# FPGA_HP_BANK.net
KiCad netlist of a schematic drawn in Altium Designer
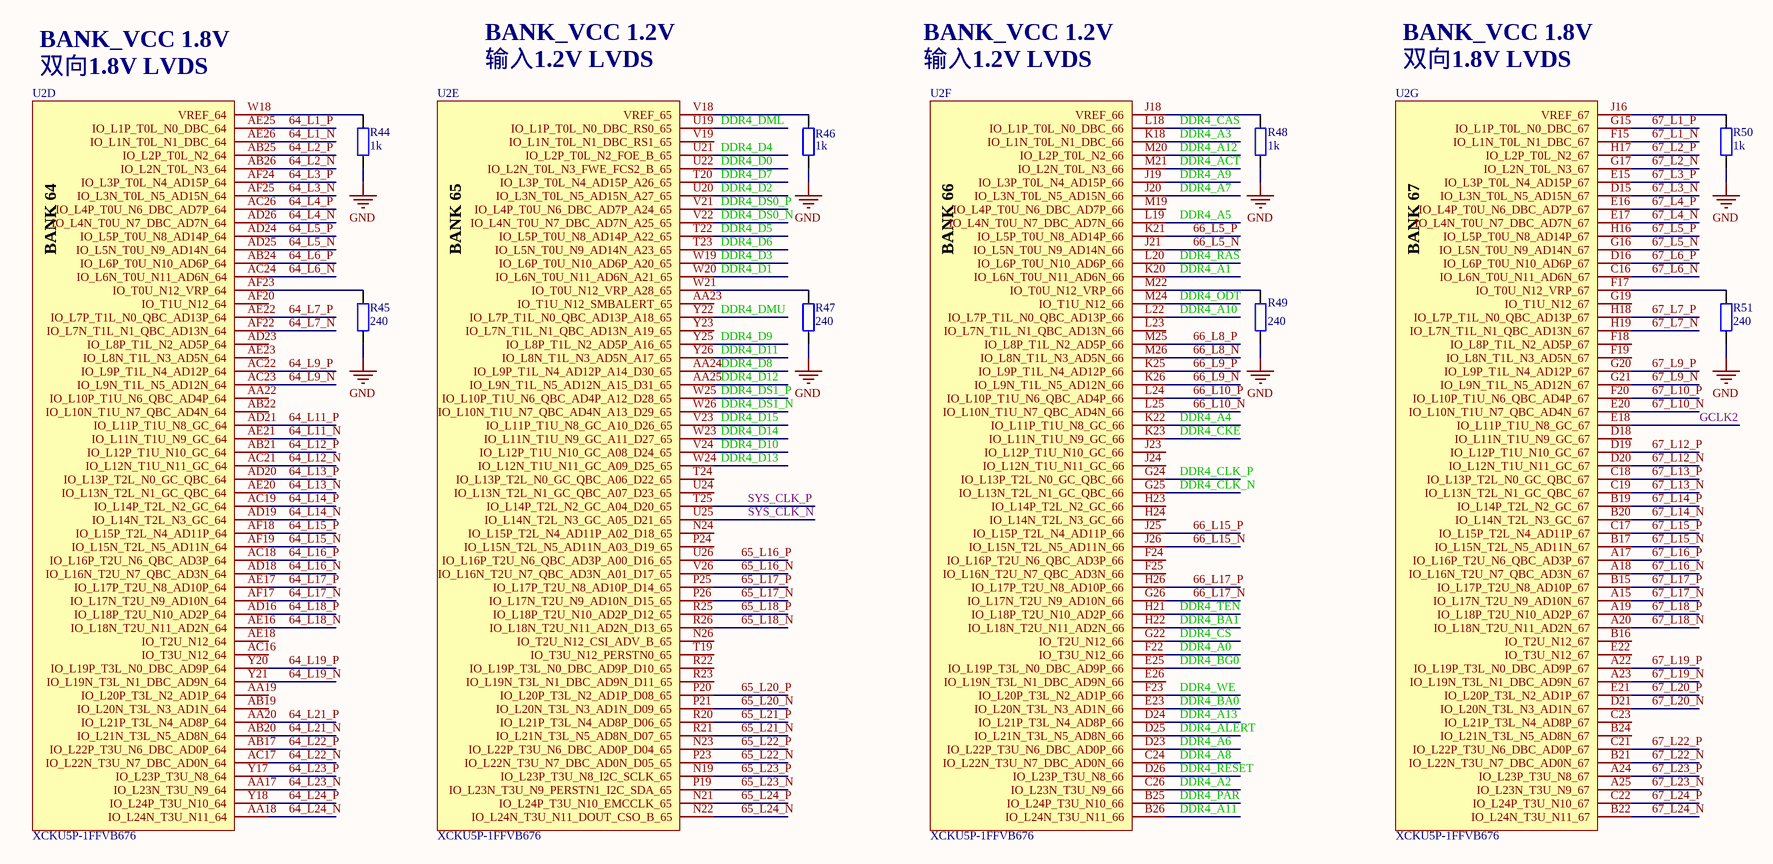
[diagram p0: FPGA HP BANK.SchDoc]

(export (version "E")
  (design (tool "Eeschema 10.0.6"))
  (components
    (comp (ref "R44") (value "1k") (footprint "0402_R_M") (libsource (lib "Common") (part "RES2")))
    (comp (ref "R45") (value "240") (footprint "0402_R_M") (libsource (lib "Common") (part "RES2")))
    (comp (ref "R46") (value "1k") (footprint "0402_R_M") (libsource (lib "Common") (part "RES2")))
    (comp (ref "R47") (value "240") (footprint "0402_R_M") (libsource (lib "Common") (part "RES2")))
    (comp (ref "R48") (value "1k") (footprint "0402_R_M") (libsource (lib "Common") (part "RES2")))
    (comp (ref "R49") (value "240") (footprint "0402_R_M") (libsource (lib "Common") (part "RES2")))
    (comp (ref "R50") (value "1k") (footprint "0402_R_M") (libsource (lib "Common") (part "RES2")))
    (comp (ref "R51") (value "240") (footprint "0402_R_M") (libsource (lib "Common") (part "RES2")))
    (comp (ref "U2") (value "XCKU5P-1FFVB676") (libsource (lib "XCKU5P-FFVB676") (part "XCKU5P-FFVB676")))
  )
  (nets
    (net (code "1") (name "/64_L1_N") (class "Default")
      (node (ref "U2") (pin "AE26") (pinfunction "IO_L1N_T0L_N1_DBC_64_AE26") (pintype "passive"))
    )
    (net (code "2") (name "/64_L1_P") (class "Default")
      (node (ref "U2") (pin "AE25") (pinfunction "IO_L1P_T0L_N0_DBC_64_AE25") (pintype "passive"))
    )
    (net (code "3") (name "/64_L2_N") (class "Default")
      (node (ref "U2") (pin "AB26") (pinfunction "IO_L2N_T0L_N3_64_AB26") (pintype "passive"))
    )
    (net (code "4") (name "/64_L2_P") (class "Default")
      (node (ref "U2") (pin "AB25") (pinfunction "IO_L2P_T0L_N2_64_AB25") (pintype "passive"))
    )
    (net (code "5") (name "/64_L3_N") (class "Default")
      (node (ref "U2") (pin "AF25") (pinfunction "IO_L3N_T0L_N5_AD15N_64_AF25") (pintype "passive"))
    )
    (net (code "6") (name "/64_L3_P") (class "Default")
      (node (ref "U2") (pin "AF24") (pinfunction "IO_L3P_T0L_N4_AD15P_64_AF24") (pintype "passive"))
    )
    (net (code "7") (name "/64_L4_N") (class "Default")
      (node (ref "U2") (pin "AD26") (pinfunction "IO_L4N_T0U_N7_DBC_AD7N_64_AD26") (pintype "passive"))
    )
    (net (code "8") (name "/64_L4_P") (class "Default")
      (node (ref "U2") (pin "AC26") (pinfunction "IO_L4P_T0U_N6_DBC_AD7P_64_AC26") (pintype "passive"))
    )
    (net (code "9") (name "/64_L5_N") (class "Default")
      (node (ref "U2") (pin "AD25") (pinfunction "IO_L5N_T0U_N9_AD14N_64_AD25") (pintype "passive"))
    )
    (net (code "10") (name "/64_L5_P") (class "Default")
      (node (ref "U2") (pin "AD24") (pinfunction "IO_L5P_T0U_N8_AD14P_64_AD24") (pintype "passive"))
    )
    (net (code "11") (name "/64_L6_N") (class "Default")
      (node (ref "U2") (pin "AC24") (pinfunction "IO_L6N_T0U_N11_AD6N_64_AC24") (pintype "passive"))
    )
    (net (code "12") (name "/64_L6_P") (class "Default")
      (node (ref "U2") (pin "AB24") (pinfunction "IO_L6P_T0U_N10_AD6P_64_AB24") (pintype "passive"))
    )
    (net (code "13") (name "/64_L7_N") (class "Default")
      (node (ref "U2") (pin "AF22") (pinfunction "IO_L7N_T1L_N1_QBC_AD13N_64_AF22") (pintype "passive"))
    )
    (net (code "14") (name "/64_L7_P") (class "Default")
      (node (ref "U2") (pin "AE22") (pinfunction "IO_L7P_T1L_N0_QBC_AD13P_64_AE22") (pintype "passive"))
    )
    (net (code "15") (name "/64_L9_N") (class "Default")
      (node (ref "U2") (pin "AC23") (pinfunction "IO_L9N_T1L_N5_AD12N_64_AC23") (pintype "passive"))
    )
    (net (code "16") (name "/64_L9_P") (class "Default")
      (node (ref "U2") (pin "AC22") (pinfunction "IO_L9P_T1L_N4_AD12P_64_AC22") (pintype "passive"))
    )
    (net (code "17") (name "/64_L11_N") (class "Default")
      (node (ref "U2") (pin "AE21") (pinfunction "IO_L11N_T1U_N9_GC_64_AE21") (pintype "passive"))
    )
    (net (code "18") (name "/64_L11_P") (class "Default")
      (node (ref "U2") (pin "AD21") (pinfunction "IO_L11P_T1U_N8_GC_64_AD21") (pintype "passive"))
    )
    (net (code "19") (name "/64_L12_N") (class "Default")
      (node (ref "U2") (pin "AC21") (pinfunction "IO_L12N_T1U_N11_GC_64_AC21") (pintype "passive"))
    )
    (net (code "20") (name "/64_L12_P") (class "Default")
      (node (ref "U2") (pin "AB21") (pinfunction "IO_L12P_T1U_N10_GC_64_AB21") (pintype "passive"))
    )
    (net (code "21") (name "/64_L13_N") (class "Default")
      (node (ref "U2") (pin "AE20") (pinfunction "IO_L13N_T2L_N1_GC_QBC_64_AE20") (pintype "passive"))
    )
    (net (code "22") (name "/64_L13_P") (class "Default")
      (node (ref "U2") (pin "AD20") (pinfunction "IO_L13P_T2L_N0_GC_QBC_64_AD20") (pintype "passive"))
    )
    (net (code "23") (name "/64_L14_N") (class "Default")
      (node (ref "U2") (pin "AD19") (pinfunction "IO_L14N_T2L_N3_GC_64_AD19") (pintype "passive"))
    )
    (net (code "24") (name "/64_L14_P") (class "Default")
      (node (ref "U2") (pin "AC19") (pinfunction "IO_L14P_T2L_N2_GC_64_AC19") (pintype "passive"))
    )
    (net (code "25") (name "/64_L15_N") (class "Default")
      (node (ref "U2") (pin "AF19") (pinfunction "IO_L15N_T2L_N5_AD11N_64_AF19") (pintype "passive"))
    )
    (net (code "26") (name "/64_L15_P") (class "Default")
      (node (ref "U2") (pin "AF18") (pinfunction "IO_L15P_T2L_N4_AD11P_64_AF18") (pintype "passive"))
    )
    (net (code "27") (name "/64_L16_N") (class "Default")
      (node (ref "U2") (pin "AD18") (pinfunction "IO_L16N_T2U_N7_QBC_AD3N_64_AD18") (pintype "passive"))
    )
    (net (code "28") (name "/64_L16_P") (class "Default")
      (node (ref "U2") (pin "AC18") (pinfunction "IO_L16P_T2U_N6_QBC_AD3P_64_AC18") (pintype "passive"))
    )
    (net (code "29") (name "/64_L17_N") (class "Default")
      (node (ref "U2") (pin "AF17") (pinfunction "IO_L17N_T2U_N9_AD10N_64_AF17") (pintype "passive"))
    )
    (net (code "30") (name "/64_L17_P") (class "Default")
      (node (ref "U2") (pin "AE17") (pinfunction "IO_L17P_T2U_N8_AD10P_64_AE17") (pintype "passive"))
    )
    (net (code "31") (name "/64_L18_N") (class "Default")
      (node (ref "U2") (pin "AE16") (pinfunction "IO_L18N_T2U_N11_AD2N_64_AE16") (pintype "passive"))
    )
    (net (code "32") (name "/64_L18_P") (class "Default")
      (node (ref "U2") (pin "AD16") (pinfunction "IO_L18P_T2U_N10_AD2P_64_AD16") (pintype "passive"))
    )
    (net (code "33") (name "/64_L19_N") (class "Default")
      (node (ref "U2") (pin "Y21") (pinfunction "IO_L19N_T3L_N1_DBC_AD9N_64_Y21") (pintype "passive"))
    )
    (net (code "34") (name "/64_L19_P") (class "Default")
      (node (ref "U2") (pin "Y20") (pinfunction "IO_L19P_T3L_N0_DBC_AD9P_64_Y20") (pintype "passive"))
    )
    (net (code "35") (name "/64_L21_N") (class "Default")
      (node (ref "U2") (pin "AB20") (pinfunction "IO_L21N_T3L_N5_AD8N_64_AB20") (pintype "passive"))
    )
    (net (code "36") (name "/64_L21_P") (class "Default")
      (node (ref "U2") (pin "AA20") (pinfunction "IO_L21P_T3L_N4_AD8P_64_AA20") (pintype "passive"))
    )
    (net (code "37") (name "/64_L22_N") (class "Default")
      (node (ref "U2") (pin "AC17") (pinfunction "IO_L22N_T3U_N7_DBC_AD0N_64_AC17") (pintype "passive"))
    )
    (net (code "38") (name "/64_L22_P") (class "Default")
      (node (ref "U2") (pin "AB17") (pinfunction "IO_L22P_T3U_N6_DBC_AD0P_64_AB17") (pintype "passive"))
    )
    (net (code "39") (name "/64_L23_N") (class "Default")
      (node (ref "U2") (pin "AA17") (pinfunction "IO_L23N_T3U_N9_64_AA17") (pintype "passive"))
    )
    (net (code "40") (name "/64_L23_P") (class "Default")
      (node (ref "U2") (pin "Y17") (pinfunction "IO_L23P_T3U_N8_64_Y17") (pintype "passive"))
    )
    (net (code "41") (name "/64_L24_N") (class "Default")
      (node (ref "U2") (pin "AA18") (pinfunction "IO_L24N_T3U_N11_64_AA18") (pintype "passive"))
    )
    (net (code "42") (name "/64_L24_P") (class "Default")
      (node (ref "U2") (pin "Y18") (pinfunction "IO_L24P_T3U_N10_64_Y18") (pintype "passive"))
    )
    (net (code "43") (name "/65_L16_N") (class "Default")
      (node (ref "U2") (pin "V26") (pinfunction "IO_L16N_T2U_N7_QBC_AD3N_A01_D17_65_V26") (pintype "passive"))
    )
    (net (code "44") (name "/65_L16_P") (class "Default")
      (node (ref "U2") (pin "U26") (pinfunction "IO_L16P_T2U_N6_QBC_AD3P_A00_D16_65_U26") (pintype "passive"))
    )
    (net (code "45") (name "/65_L17_N") (class "Default")
      (node (ref "U2") (pin "P26") (pinfunction "IO_L17N_T2U_N9_AD10N_D15_65_P26") (pintype "passive"))
    )
    (net (code "46") (name "/65_L17_P") (class "Default")
      (node (ref "U2") (pin "P25") (pinfunction "IO_L17P_T2U_N8_AD10P_D14_65_P25") (pintype "passive"))
    )
    (net (code "47") (name "/65_L18_N") (class "Default")
      (node (ref "U2") (pin "R26") (pinfunction "IO_L18N_T2U_N11_AD2N_D13_65_R26") (pintype "passive"))
    )
    (net (code "48") (name "/65_L18_P") (class "Default")
      (node (ref "U2") (pin "R25") (pinfunction "IO_L18P_T2U_N10_AD2P_D12_65_R25") (pintype "passive"))
    )
    (net (code "49") (name "/65_L20_N") (class "Default")
      (node (ref "U2") (pin "P21") (pinfunction "IO_L20N_T3L_N3_AD1N_D09_65_P21") (pintype "passive"))
    )
    (net (code "50") (name "/65_L20_P") (class "Default")
      (node (ref "U2") (pin "P20") (pinfunction "IO_L20P_T3L_N2_AD1P_D08_65_P20") (pintype "passive"))
    )
    (net (code "51") (name "/65_L21_N") (class "Default")
      (node (ref "U2") (pin "R21") (pinfunction "IO_L21N_T3L_N5_AD8N_D07_65_R21") (pintype "passive"))
    )
    (net (code "52") (name "/65_L21_P") (class "Default")
      (node (ref "U2") (pin "R20") (pinfunction "IO_L21P_T3L_N4_AD8P_D06_65_R20") (pintype "passive"))
    )
    (net (code "53") (name "/65_L22_N") (class "Default")
      (node (ref "U2") (pin "P23") (pinfunction "IO_L22N_T3U_N7_DBC_AD0N_D05_65_P23") (pintype "passive"))
    )
    (net (code "54") (name "/65_L22_P") (class "Default")
      (node (ref "U2") (pin "N23") (pinfunction "IO_L22P_T3U_N6_DBC_AD0P_D04_65_N23") (pintype "passive"))
    )
    (net (code "55") (name "/65_L23_N") (class "Default")
      (node (ref "U2") (pin "P19") (pinfunction "IO_L23N_T3U_N9_PERSTN1_I2C_SDA_65_P19") (pintype "passive"))
    )
    (net (code "56") (name "/65_L23_P") (class "Default")
      (node (ref "U2") (pin "N19") (pinfunction "IO_L23P_T3U_N8_I2C_SCLK_65_N19") (pintype "passive"))
    )
    (net (code "57") (name "/65_L24_N") (class "Default")
      (node (ref "U2") (pin "N22") (pinfunction "IO_L24N_T3U_N11_DOUT_CSO_B_65_N22") (pintype "passive"))
    )
    (net (code "58") (name "/65_L24_P") (class "Default")
      (node (ref "U2") (pin "N21") (pinfunction "IO_L24P_T3U_N10_EMCCLK_65_N21") (pintype "passive"))
    )
    (net (code "59") (name "/66_L5_N") (class "Default")
      (node (ref "U2") (pin "J21") (pinfunction "IO_L5N_T0U_N9_AD14N_66_J21") (pintype "passive"))
    )
    (net (code "60") (name "/66_L5_P") (class "Default")
      (node (ref "U2") (pin "K21") (pinfunction "IO_L5P_T0U_N8_AD14P_66_K21") (pintype "passive"))
    )
    (net (code "61") (name "/66_L8_N") (class "Default")
      (node (ref "U2") (pin "M26") (pinfunction "IO_L8N_T1L_N3_AD5N_66_M26") (pintype "passive"))
    )
    (net (code "62") (name "/66_L8_P") (class "Default")
      (node (ref "U2") (pin "M25") (pinfunction "IO_L8P_T1L_N2_AD5P_66_M25") (pintype "passive"))
    )
    (net (code "63") (name "/66_L9_N") (class "Default")
      (node (ref "U2") (pin "K26") (pinfunction "IO_L9N_T1L_N5_AD12N_66_K26") (pintype "passive"))
    )
    (net (code "64") (name "/66_L9_P") (class "Default")
      (node (ref "U2") (pin "K25") (pinfunction "IO_L9P_T1L_N4_AD12P_66_K25") (pintype "passive"))
    )
    (net (code "65") (name "/66_L10_N") (class "Default")
      (node (ref "U2") (pin "L25") (pinfunction "IO_L10N_T1U_N7_QBC_AD4N_66_L25") (pintype "passive"))
    )
    (net (code "66") (name "/66_L10_P") (class "Default")
      (node (ref "U2") (pin "L24") (pinfunction "IO_L10P_T1U_N6_QBC_AD4P_66_L24") (pintype "passive"))
    )
    (net (code "67") (name "/66_L15_N") (class "Default")
      (node (ref "U2") (pin "J26") (pinfunction "IO_L15N_T2L_N5_AD11N_66_J26") (pintype "passive"))
    )
    (net (code "68") (name "/66_L15_P") (class "Default")
      (node (ref "U2") (pin "J25") (pinfunction "IO_L15P_T2L_N4_AD11P_66_J25") (pintype "passive"))
    )
    (net (code "69") (name "/66_L17_N") (class "Default")
      (node (ref "U2") (pin "G26") (pinfunction "IO_L17N_T2U_N9_AD10N_66_G26") (pintype "passive"))
    )
    (net (code "70") (name "/66_L17_P") (class "Default")
      (node (ref "U2") (pin "H26") (pinfunction "IO_L17P_T2U_N8_AD10P_66_H26") (pintype "passive"))
    )
    (net (code "71") (name "/67_L1_N") (class "Default")
      (node (ref "U2") (pin "F15") (pinfunction "IO_L1N_T0L_N1_DBC_67_F15") (pintype "passive"))
    )
    (net (code "72") (name "/67_L1_P") (class "Default")
      (node (ref "U2") (pin "G15") (pinfunction "IO_L1P_T0L_N0_DBC_67_G15") (pintype "passive"))
    )
    (net (code "73") (name "/67_L2_N") (class "Default")
      (node (ref "U2") (pin "G17") (pinfunction "IO_L2N_T0L_N3_67_G17") (pintype "passive"))
    )
    (net (code "74") (name "/67_L2_P") (class "Default")
      (node (ref "U2") (pin "H17") (pinfunction "IO_L2P_T0L_N2_67_H17") (pintype "passive"))
    )
    (net (code "75") (name "/67_L3_N") (class "Default")
      (node (ref "U2") (pin "D15") (pinfunction "IO_L3N_T0L_N5_AD15N_67_D15") (pintype "passive"))
    )
    (net (code "76") (name "/67_L3_P") (class "Default")
      (node (ref "U2") (pin "E15") (pinfunction "IO_L3P_T0L_N4_AD15P_67_E15") (pintype "passive"))
    )
    (net (code "77") (name "/67_L4_N") (class "Default")
      (node (ref "U2") (pin "E17") (pinfunction "IO_L4N_T0U_N7_DBC_AD7N_67_E17") (pintype "passive"))
    )
    (net (code "78") (name "/67_L4_P") (class "Default")
      (node (ref "U2") (pin "E16") (pinfunction "IO_L4P_T0U_N6_DBC_AD7P_67_E16") (pintype "passive"))
    )
    (net (code "79") (name "/67_L5_N") (class "Default")
      (node (ref "U2") (pin "G16") (pinfunction "IO_L5N_T0U_N9_AD14N_67_G16") (pintype "passive"))
    )
    (net (code "80") (name "/67_L5_P") (class "Default")
      (node (ref "U2") (pin "H16") (pinfunction "IO_L5P_T0U_N8_AD14P_67_H16") (pintype "passive"))
    )
    (net (code "81") (name "/67_L6_N") (class "Default")
      (node (ref "U2") (pin "C16") (pinfunction "IO_L6N_T0U_N11_AD6N_67_C16") (pintype "passive"))
    )
    (net (code "82") (name "/67_L6_P") (class "Default")
      (node (ref "U2") (pin "D16") (pinfunction "IO_L6P_T0U_N10_AD6P_67_D16") (pintype "passive"))
    )
    (net (code "83") (name "/67_L7_N") (class "Default")
      (node (ref "U2") (pin "H19") (pinfunction "IO_L7N_T1L_N1_QBC_AD13N_67_H19") (pintype "passive"))
    )
    (net (code "84") (name "/67_L7_P") (class "Default")
      (node (ref "U2") (pin "H18") (pinfunction "IO_L7P_T1L_N0_QBC_AD13P_67_H18") (pintype "passive"))
    )
    (net (code "85") (name "/67_L9_N") (class "Default")
      (node (ref "U2") (pin "G21") (pinfunction "IO_L9N_T1L_N5_AD12N_67_G21") (pintype "passive"))
    )
    (net (code "86") (name "/67_L9_P") (class "Default")
      (node (ref "U2") (pin "G20") (pinfunction "IO_L9P_T1L_N4_AD12P_67_G20") (pintype "passive"))
    )
    (net (code "87") (name "/67_L10_N") (class "Default")
      (node (ref "U2") (pin "E20") (pinfunction "IO_L10N_T1U_N7_QBC_AD4N_67_E20") (pintype "passive"))
    )
    (net (code "88") (name "/67_L10_P") (class "Default")
      (node (ref "U2") (pin "F20") (pinfunction "IO_L10P_T1U_N6_QBC_AD4P_67_F20") (pintype "passive"))
    )
    (net (code "89") (name "/67_L12_N") (class "Default")
      (node (ref "U2") (pin "D20") (pinfunction "IO_L12N_T1U_N11_GC_67_D20") (pintype "passive"))
    )
    (net (code "90") (name "/67_L12_P") (class "Default")
      (node (ref "U2") (pin "D19") (pinfunction "IO_L12P_T1U_N10_GC_67_D19") (pintype "passive"))
    )
    (net (code "91") (name "/67_L13_N") (class "Default")
      (node (ref "U2") (pin "C19") (pinfunction "IO_L13N_T2L_N1_GC_QBC_67_C19") (pintype "passive"))
    )
    (net (code "92") (name "/67_L13_P") (class "Default")
      (node (ref "U2") (pin "C18") (pinfunction "IO_L13P_T2L_N0_GC_QBC_67_C18") (pintype "passive"))
    )
    (net (code "93") (name "/67_L14_N") (class "Default")
      (node (ref "U2") (pin "B20") (pinfunction "IO_L14N_T2L_N3_GC_67_B20") (pintype "passive"))
    )
    (net (code "94") (name "/67_L14_P") (class "Default")
      (node (ref "U2") (pin "B19") (pinfunction "IO_L14P_T2L_N2_GC_67_B19") (pintype "passive"))
    )
    (net (code "95") (name "/67_L15_N") (class "Default")
      (node (ref "U2") (pin "B17") (pinfunction "IO_L15N_T2L_N5_AD11N_67_B17") (pintype "passive"))
    )
    (net (code "96") (name "/67_L15_P") (class "Default")
      (node (ref "U2") (pin "C17") (pinfunction "IO_L15P_T2L_N4_AD11P_67_C17") (pintype "passive"))
    )
    (net (code "97") (name "/67_L16_N") (class "Default")
      (node (ref "U2") (pin "A18") (pinfunction "IO_L16N_T2U_N7_QBC_AD3N_67_A18") (pintype "passive"))
    )
    (net (code "98") (name "/67_L16_P") (class "Default")
      (node (ref "U2") (pin "A17") (pinfunction "IO_L16P_T2U_N6_QBC_AD3P_67_A17") (pintype "passive"))
    )
    (net (code "99") (name "/67_L17_N") (class "Default")
      (node (ref "U2") (pin "A15") (pinfunction "IO_L17N_T2U_N9_AD10N_67_A15") (pintype "passive"))
    )
    (net (code "100") (name "/67_L17_P") (class "Default")
      (node (ref "U2") (pin "B15") (pinfunction "IO_L17P_T2U_N8_AD10P_67_B15") (pintype "passive"))
    )
    (net (code "101") (name "/67_L18_N") (class "Default")
      (node (ref "U2") (pin "A20") (pinfunction "IO_L18N_T2U_N11_AD2N_67_A20") (pintype "passive"))
    )
    (net (code "102") (name "/67_L18_P") (class "Default")
      (node (ref "U2") (pin "A19") (pinfunction "IO_L18P_T2U_N10_AD2P_67_A19") (pintype "passive"))
    )
    (net (code "103") (name "/67_L19_N") (class "Default")
      (node (ref "U2") (pin "A23") (pinfunction "IO_L19N_T3L_N1_DBC_AD9N_67_A23") (pintype "passive"))
    )
    (net (code "104") (name "/67_L19_P") (class "Default")
      (node (ref "U2") (pin "A22") (pinfunction "IO_L19P_T3L_N0_DBC_AD9P_67_A22") (pintype "passive"))
    )
    (net (code "105") (name "/67_L20_N") (class "Default")
      (node (ref "U2") (pin "D21") (pinfunction "IO_L20N_T3L_N3_AD1N_67_D21") (pintype "passive"))
    )
    (net (code "106") (name "/67_L20_P") (class "Default")
      (node (ref "U2") (pin "E21") (pinfunction "IO_L20P_T3L_N2_AD1P_67_E21") (pintype "passive"))
    )
    (net (code "107") (name "/67_L22_N") (class "Default")
      (node (ref "U2") (pin "B21") (pinfunction "IO_L22N_T3U_N7_DBC_AD0N_67_B21") (pintype "passive"))
    )
    (net (code "108") (name "/67_L22_P") (class "Default")
      (node (ref "U2") (pin "C21") (pinfunction "IO_L22P_T3U_N6_DBC_AD0P_67_C21") (pintype "passive"))
    )
    (net (code "109") (name "/67_L23_N") (class "Default")
      (node (ref "U2") (pin "A25") (pinfunction "IO_L23N_T3U_N9_67_A25") (pintype "passive"))
    )
    (net (code "110") (name "/67_L23_P") (class "Default")
      (node (ref "U2") (pin "A24") (pinfunction "IO_L23P_T3U_N8_67_A24") (pintype "passive"))
    )
    (net (code "111") (name "/67_L24_N") (class "Default")
      (node (ref "U2") (pin "B22") (pinfunction "IO_L24N_T3U_N11_67_B22") (pintype "passive"))
    )
    (net (code "112") (name "/67_L24_P") (class "Default")
      (node (ref "U2") (pin "C22") (pinfunction "IO_L24P_T3U_N10_67_C22") (pintype "passive"))
    )
    (net (code "113") (name "/DDR4_A0") (class "Default")
      (node (ref "U2") (pin "F22") (pinfunction "IO_T3U_N12_66_F22") (pintype "passive"))
    )
    (net (code "114") (name "/DDR4_A1") (class "Default")
      (node (ref "U2") (pin "K20") (pinfunction "IO_L6N_T0U_N11_AD6N_66_K20") (pintype "passive"))
    )
    (net (code "115") (name "/DDR4_A2") (class "Default")
      (node (ref "U2") (pin "C26") (pinfunction "IO_L23N_T3U_N9_66_C26") (pintype "passive"))
    )
    (net (code "116") (name "/DDR4_A3") (class "Default")
      (node (ref "U2") (pin "K18") (pinfunction "IO_L1N_T0L_N1_DBC_66_K18") (pintype "passive"))
    )
    (net (code "117") (name "/DDR4_A4") (class "Default")
      (node (ref "U2") (pin "K22") (pinfunction "IO_L11P_T1U_N8_GC_66_K22") (pintype "passive"))
    )
    (net (code "118") (name "/DDR4_A5") (class "Default")
      (node (ref "U2") (pin "L19") (pinfunction "IO_L4N_T0U_N7_DBC_AD7N_66_L19") (pintype "passive"))
    )
    (net (code "119") (name "/DDR4_A6") (class "Default")
      (node (ref "U2") (pin "D23") (pinfunction "IO_L22P_T3U_N6_DBC_AD0P_66_D23") (pintype "passive"))
    )
    (net (code "120") (name "/DDR4_A7") (class "Default")
      (node (ref "U2") (pin "J20") (pinfunction "IO_L3N_T0L_N5_AD15N_66_J20") (pintype "passive"))
    )
    (net (code "121") (name "/DDR4_A8") (class "Default")
      (node (ref "U2") (pin "C24") (pinfunction "IO_L22N_T3U_N7_DBC_AD0N_66_C24") (pintype "passive"))
    )
    (net (code "122") (name "/DDR4_A9") (class "Default")
      (node (ref "U2") (pin "J19") (pinfunction "IO_L3P_T0L_N4_AD15P_66_J19") (pintype "passive"))
    )
    (net (code "123") (name "/DDR4_A10") (class "Default")
      (node (ref "U2") (pin "L22") (pinfunction "IO_L7P_T1L_N0_QBC_AD13P_66_L22") (pintype "passive"))
    )
    (net (code "124") (name "/DDR4_A11") (class "Default")
      (node (ref "U2") (pin "B26") (pinfunction "IO_L24N_T3U_N11_66_B26") (pintype "passive"))
    )
    (net (code "125") (name "/DDR4_A12") (class "Default")
      (node (ref "U2") (pin "M20") (pinfunction "IO_L2P_T0L_N2_66_M20") (pintype "passive"))
    )
    (net (code "126") (name "/DDR4_A13") (class "Default")
      (node (ref "U2") (pin "D24") (pinfunction "IO_L21P_T3L_N4_AD8P_66_D24") (pintype "passive"))
    )
    (net (code "127") (name "/DDR4_ACT") (class "Default")
      (node (ref "U2") (pin "M21") (pinfunction "IO_L2N_T0L_N3_66_M21") (pintype "passive"))
    )
    (net (code "128") (name "/DDR4_ALERT") (class "Default")
      (node (ref "U2") (pin "D25") (pinfunction "IO_L21N_T3L_N5_AD8N_66_D25") (pintype "passive"))
    )
    (net (code "129") (name "/DDR4_BA0") (class "Default")
      (node (ref "U2") (pin "E23") (pinfunction "IO_L20N_T3L_N3_AD1N_66_E23") (pintype "passive"))
    )
    (net (code "130") (name "/DDR4_BA1") (class "Default")
      (node (ref "U2") (pin "H22") (pinfunction "IO_L18N_T2U_N11_AD2N_66_H22") (pintype "passive"))
    )
    (net (code "131") (name "/DDR4_BG0") (class "Default")
      (node (ref "U2") (pin "E25") (pinfunction "IO_L19P_T3L_N0_DBC_AD9P_66_E25") (pintype "passive"))
    )
    (net (code "132") (name "/DDR4_CAS") (class "Default")
      (node (ref "U2") (pin "L18") (pinfunction "IO_L1P_T0L_N0_DBC_66_L18") (pintype "passive"))
    )
    (net (code "133") (name "/DDR4_CKE") (class "Default")
      (node (ref "U2") (pin "K23") (pinfunction "IO_L11N_T1U_N9_GC_66_K23") (pintype "passive"))
    )
    (net (code "134") (name "/DDR4_CLK_N") (class "Default")
      (node (ref "U2") (pin "G25") (pinfunction "IO_L13N_T2L_N1_GC_QBC_66_G25") (pintype "passive"))
    )
    (net (code "135") (name "/DDR4_CLK_P") (class "Default")
      (node (ref "U2") (pin "G24") (pinfunction "IO_L13P_T2L_N0_GC_QBC_66_G24") (pintype "passive"))
    )
    (net (code "136") (name "/DDR4_CS") (class "Default")
      (node (ref "U2") (pin "G22") (pinfunction "IO_T2U_N12_66_G22") (pintype "passive"))
    )
    (net (code "137") (name "/DDR4_D0") (class "Default")
      (node (ref "U2") (pin "U22") (pinfunction "IO_L2N_T0L_N3_FWE_FCS2_B_65_U22") (pintype "passive"))
    )
    (net (code "138") (name "/DDR4_D1") (class "Default")
      (node (ref "U2") (pin "W20") (pinfunction "IO_L6N_T0U_N11_AD6N_A21_65_W20") (pintype "passive"))
    )
    (net (code "139") (name "/DDR4_D2") (class "Default")
      (node (ref "U2") (pin "U20") (pinfunction "IO_L3N_T0L_N5_AD15N_A27_65_U20") (pintype "passive"))
    )
    (net (code "140") (name "/DDR4_D3") (class "Default")
      (node (ref "U2") (pin "W19") (pinfunction "IO_L6P_T0U_N10_AD6P_A20_65_W19") (pintype "passive"))
    )
    (net (code "141") (name "/DDR4_D4") (class "Default")
      (node (ref "U2") (pin "U21") (pinfunction "IO_L2P_T0L_N2_FOE_B_65_U21") (pintype "passive"))
    )
    (net (code "142") (name "/DDR4_D5") (class "Default")
      (node (ref "U2") (pin "T22") (pinfunction "IO_L5P_T0U_N8_AD14P_A22_65_T22") (pintype "passive"))
    )
    (net (code "143") (name "/DDR4_D6") (class "Default")
      (node (ref "U2") (pin "T23") (pinfunction "IO_L5N_T0U_N9_AD14N_A23_65_T23") (pintype "passive"))
    )
    (net (code "144") (name "/DDR4_D7") (class "Default")
      (node (ref "U2") (pin "T20") (pinfunction "IO_L3P_T0L_N4_AD15P_A26_65_T20") (pintype "passive"))
    )
    (net (code "145") (name "/DDR4_D8") (class "Default")
      (node (ref "U2") (pin "AA24") (pinfunction "IO_L9P_T1L_N4_AD12P_A14_D30_65_AA24") (pintype "passive"))
    )
    (net (code "146") (name "/DDR4_D9") (class "Default")
      (node (ref "U2") (pin "Y25") (pinfunction "IO_L8P_T1L_N2_AD5P_A16_65_Y25") (pintype "passive"))
    )
    (net (code "147") (name "/DDR4_D10") (class "Default")
      (node (ref "U2") (pin "V24") (pinfunction "IO_L12P_T1U_N10_GC_A08_D24_65_V24") (pintype "passive"))
    )
    (net (code "148") (name "/DDR4_D11") (class "Default")
      (node (ref "U2") (pin "Y26") (pinfunction "IO_L8N_T1L_N3_AD5N_A17_65_Y26") (pintype "passive"))
    )
    (net (code "149") (name "/DDR4_D12") (class "Default")
      (node (ref "U2") (pin "AA25") (pinfunction "IO_L9N_T1L_N5_AD12N_A15_D31_65_AA25") (pintype "passive"))
    )
    (net (code "150") (name "/DDR4_D13") (class "Default")
      (node (ref "U2") (pin "W24") (pinfunction "IO_L12N_T1U_N11_GC_A09_D25_65_W24") (pintype "passive"))
    )
    (net (code "151") (name "/DDR4_D14") (class "Default")
      (node (ref "U2") (pin "W23") (pinfunction "IO_L11N_T1U_N9_GC_A11_D27_65_W23") (pintype "passive"))
    )
    (net (code "152") (name "/DDR4_D15") (class "Default")
      (node (ref "U2") (pin "V23") (pinfunction "IO_L11P_T1U_N8_GC_A10_D26_65_V23") (pintype "passive"))
    )
    (net (code "153") (name "/DDR4_DML") (class "Default")
      (node (ref "U2") (pin "U19") (pinfunction "IO_L1P_T0L_N0_DBC_RS0_65_U19") (pintype "passive"))
    )
    (net (code "154") (name "/DDR4_DMU") (class "Default")
      (node (ref "U2") (pin "Y22") (pinfunction "IO_L7P_T1L_N0_QBC_AD13P_A18_65_Y22") (pintype "passive"))
    )
    (net (code "155") (name "/DDR4_DS0_N") (class "Default")
      (node (ref "U2") (pin "V22") (pinfunction "IO_L4N_T0U_N7_DBC_AD7N_A25_65_V22") (pintype "passive"))
    )
    (net (code "156") (name "/DDR4_DS0_P") (class "Default")
      (node (ref "U2") (pin "V21") (pinfunction "IO_L4P_T0U_N6_DBC_AD7P_A24_65_V21") (pintype "passive"))
    )
    (net (code "157") (name "/DDR4_DS1_N") (class "Default")
      (node (ref "U2") (pin "W26") (pinfunction "IO_L10N_T1U_N7_QBC_AD4N_A13_D29_65_W26") (pintype "passive"))
    )
    (net (code "158") (name "/DDR4_DS1_P") (class "Default")
      (node (ref "U2") (pin "W25") (pinfunction "IO_L10P_T1U_N6_QBC_AD4P_A12_D28_65_W25") (pintype "passive"))
    )
    (net (code "159") (name "/DDR4_ODT") (class "Default")
      (node (ref "U2") (pin "M24") (pinfunction "IO_T1U_N12_66_M24") (pintype "passive"))
    )
    (net (code "160") (name "/DDR4_PAR") (class "Default")
      (node (ref "U2") (pin "B25") (pinfunction "IO_L24P_T3U_N10_66_B25") (pintype "passive"))
    )
    (net (code "161") (name "/DDR4_RAS") (class "Default")
      (node (ref "U2") (pin "L20") (pinfunction "IO_L6P_T0U_N10_AD6P_66_L20") (pintype "passive"))
    )
    (net (code "162") (name "/DDR4_RESET") (class "Default")
      (node (ref "U2") (pin "D26") (pinfunction "IO_L23P_T3U_N8_66_D26") (pintype "passive"))
    )
    (net (code "163") (name "/DDR4_TEN") (class "Default")
      (node (ref "U2") (pin "H21") (pinfunction "IO_L18P_T2U_N10_AD2P_66_H21") (pintype "passive"))
    )
    (net (code "164") (name "/DDR4_WE") (class "Default")
      (node (ref "U2") (pin "F23") (pinfunction "IO_L20P_T3L_N2_AD1P_66_F23") (pintype "passive"))
    )
    (net (code "165") (name "/GCLK2") (class "Default")
      (node (ref "U2") (pin "E18") (pinfunction "IO_L11P_T1U_N8_GC_67_E18") (pintype "passive"))
    )
    (net (code "166") (name "/SYS_CLK_N") (class "Default")
      (node (ref "U2") (pin "U25") (pinfunction "IO_L14N_T2L_N3_GC_A05_D21_65_U25") (pintype "passive"))
    )
    (net (code "167") (name "/SYS_CLK_P") (class "Default")
      (node (ref "U2") (pin "T25") (pinfunction "IO_L14P_T2L_N2_GC_A04_D20_65_T25") (pintype "passive"))
    )
    (net (code "168") (name "GND") (class "Default")
      (node (ref "R44") (pin "2") (pintype "passive"))
      (node (ref "R45") (pin "2") (pintype "passive"))
      (node (ref "R46") (pin "2") (pintype "passive"))
      (node (ref "R47") (pin "2") (pintype "passive"))
      (node (ref "R48") (pin "2") (pintype "passive"))
      (node (ref "R49") (pin "2") (pintype "passive"))
      (node (ref "R50") (pin "2") (pintype "passive"))
      (node (ref "R51") (pin "2") (pintype "passive"))
    )
    (net (code "169") (name "Net-(U2D-IO_T0U_N12_VRP_64)") (class "Default")
      (node (ref "R45") (pin "1") (pintype "passive"))
      (node (ref "U2") (pin "AF23") (pinfunction "IO_T0U_N12_VRP_64_AF23") (pintype "passive"))
    )
    (net (code "170") (name "Net-(U2D-VREF_64)") (class "Default")
      (node (ref "R44") (pin "1") (pintype "passive"))
      (node (ref "U2") (pin "W18") (pinfunction "VREF_64_W18") (pintype "passive"))
    )
    (net (code "171") (name "Net-(U2E-IO_T0U_N12_VRP_A28_65)") (class "Default")
      (node (ref "R47") (pin "1") (pintype "passive"))
      (node (ref "U2") (pin "W21") (pinfunction "IO_T0U_N12_VRP_A28_65_W21") (pintype "passive"))
    )
    (net (code "172") (name "Net-(U2E-VREF_65)") (class "Default")
      (node (ref "R46") (pin "1") (pintype "passive"))
      (node (ref "U2") (pin "V18") (pinfunction "VREF_65_V18") (pintype "passive"))
    )
    (net (code "173") (name "Net-(U2F-IO_T0U_N12_VRP_66)") (class "Default")
      (node (ref "R49") (pin "1") (pintype "passive"))
      (node (ref "U2") (pin "M22") (pinfunction "IO_T0U_N12_VRP_66_M22") (pintype "passive"))
    )
    (net (code "174") (name "Net-(U2F-VREF_66)") (class "Default")
      (node (ref "R48") (pin "1") (pintype "passive"))
      (node (ref "U2") (pin "J18") (pinfunction "VREF_66_J18") (pintype "passive"))
    )
    (net (code "175") (name "Net-(U2G-IO_T0U_N12_VRP_67)") (class "Default")
      (node (ref "R51") (pin "1") (pintype "passive"))
      (node (ref "U2") (pin "F17") (pinfunction "IO_T0U_N12_VRP_67_F17") (pintype "passive"))
    )
    (net (code "176") (name "Net-(U2G-VREF_67)") (class "Default")
      (node (ref "R50") (pin "1") (pintype "passive"))
      (node (ref "U2") (pin "J16") (pinfunction "VREF_67_J16") (pintype "passive"))
    )
    (net (code "177") (name "unconnected-(U2D-IO_L8N_T1L_N3_AD5N_64-PadAE23)") (class "Default")
      (node (ref "U2") (pin "AE23") (pinfunction "IO_L8N_T1L_N3_AD5N_64_AE23") (pintype "passive"))
    )
    (net (code "178") (name "unconnected-(U2D-IO_L8P_T1L_N2_AD5P_64-PadAD23)") (class "Default")
      (node (ref "U2") (pin "AD23") (pinfunction "IO_L8P_T1L_N2_AD5P_64_AD23") (pintype "passive"))
    )
    (net (code "179") (name "unconnected-(U2D-IO_L10N_T1U_N7_QBC_AD4N_64-PadAB22)") (class "Default")
      (node (ref "U2") (pin "AB22") (pinfunction "IO_L10N_T1U_N7_QBC_AD4N_64_AB22") (pintype "passive"))
    )
    (net (code "180") (name "unconnected-(U2D-IO_L10P_T1U_N6_QBC_AD4P_64-PadAA22)") (class "Default")
      (node (ref "U2") (pin "AA22") (pinfunction "IO_L10P_T1U_N6_QBC_AD4P_64_AA22") (pintype "passive"))
    )
    (net (code "181") (name "unconnected-(U2D-IO_L20N_T3L_N3_AD1N_64-PadAB19)") (class "Default")
      (node (ref "U2") (pin "AB19") (pinfunction "IO_L20N_T3L_N3_AD1N_64_AB19") (pintype "passive"))
    )
    (net (code "182") (name "unconnected-(U2D-IO_L20P_T3L_N2_AD1P_64-PadAA19)") (class "Default")
      (node (ref "U2") (pin "AA19") (pinfunction "IO_L20P_T3L_N2_AD1P_64_AA19") (pintype "passive"))
    )
    (net (code "183") (name "unconnected-(U2D-IO_T1U_N12_64-PadAF20)") (class "Default")
      (node (ref "U2") (pin "AF20") (pinfunction "IO_T1U_N12_64_AF20") (pintype "passive"))
    )
    (net (code "184") (name "unconnected-(U2D-IO_T2U_N12_64-PadAE18)") (class "Default")
      (node (ref "U2") (pin "AE18") (pinfunction "IO_T2U_N12_64_AE18") (pintype "passive"))
    )
    (net (code "185") (name "unconnected-(U2D-IO_T3U_N12_64-PadAC16)") (class "Default")
      (node (ref "U2") (pin "AC16") (pinfunction "IO_T3U_N12_64_AC16") (pintype "passive"))
    )
    (net (code "186") (name "unconnected-(U2E-IO_L1N_T0L_N1_DBC_RS1_65-PadV19)") (class "Default")
      (node (ref "U2") (pin "V19") (pinfunction "IO_L1N_T0L_N1_DBC_RS1_65_V19") (pintype "passive"))
    )
    (net (code "187") (name "unconnected-(U2E-IO_L7N_T1L_N1_QBC_AD13N_A19_65-PadY23)") (class "Default")
      (node (ref "U2") (pin "Y23") (pinfunction "IO_L7N_T1L_N1_QBC_AD13N_A19_65_Y23") (pintype "passive"))
    )
    (net (code "188") (name "unconnected-(U2E-IO_L13N_T2L_N1_GC_QBC_A07_D23_65-PadU24)") (class "Default")
      (node (ref "U2") (pin "U24") (pinfunction "IO_L13N_T2L_N1_GC_QBC_A07_D23_65_U24") (pintype "passive"))
    )
    (net (code "189") (name "unconnected-(U2E-IO_L13P_T2L_N0_GC_QBC_A06_D22_65-PadT24)") (class "Default")
      (node (ref "U2") (pin "T24") (pinfunction "IO_L13P_T2L_N0_GC_QBC_A06_D22_65_T24") (pintype "passive"))
    )
    (net (code "190") (name "unconnected-(U2E-IO_L15N_T2L_N5_AD11N_A03_D19_65-PadP24)") (class "Default")
      (node (ref "U2") (pin "P24") (pinfunction "IO_L15N_T2L_N5_AD11N_A03_D19_65_P24") (pintype "passive"))
    )
    (net (code "191") (name "unconnected-(U2E-IO_L15P_T2L_N4_AD11P_A02_D18_65-PadN24)") (class "Default")
      (node (ref "U2") (pin "N24") (pinfunction "IO_L15P_T2L_N4_AD11P_A02_D18_65_N24") (pintype "passive"))
    )
    (net (code "192") (name "unconnected-(U2E-IO_L19N_T3L_N1_DBC_AD9N_D11_65-PadR23)") (class "Default")
      (node (ref "U2") (pin "R23") (pinfunction "IO_L19N_T3L_N1_DBC_AD9N_D11_65_R23") (pintype "passive"))
    )
    (net (code "193") (name "unconnected-(U2E-IO_L19P_T3L_N0_DBC_AD9P_D10_65-PadR22)") (class "Default")
      (node (ref "U2") (pin "R22") (pinfunction "IO_L19P_T3L_N0_DBC_AD9P_D10_65_R22") (pintype "passive"))
    )
    (net (code "194") (name "unconnected-(U2E-IO_T1U_N12_SMBALERT_65-PadAA23)") (class "Default")
      (node (ref "U2") (pin "AA23") (pinfunction "IO_T1U_N12_SMBALERT_65_AA23") (pintype "passive"))
    )
    (net (code "195") (name "unconnected-(U2E-IO_T2U_N12_CSI_ADV_B_65-PadN26)") (class "Default")
      (node (ref "U2") (pin "N26") (pinfunction "IO_T2U_N12_CSI_ADV_B_65_N26") (pintype "passive"))
    )
    (net (code "196") (name "unconnected-(U2E-IO_T3U_N12_PERSTN0_65-PadT19)") (class "Default")
      (node (ref "U2") (pin "T19") (pinfunction "IO_T3U_N12_PERSTN0_65_T19") (pintype "passive"))
    )
    (net (code "197") (name "unconnected-(U2F-IO_L4P_T0U_N6_DBC_AD7P_66-PadM19)") (class "Default")
      (node (ref "U2") (pin "M19") (pinfunction "IO_L4P_T0U_N6_DBC_AD7P_66_M19") (pintype "passive"))
    )
    (net (code "198") (name "unconnected-(U2F-IO_L7N_T1L_N1_QBC_AD13N_66-PadL23)") (class "Default")
      (node (ref "U2") (pin "L23") (pinfunction "IO_L7N_T1L_N1_QBC_AD13N_66_L23") (pintype "passive"))
    )
    (net (code "199") (name "unconnected-(U2F-IO_L12N_T1U_N11_GC_66-PadJ24)") (class "Default")
      (node (ref "U2") (pin "J24") (pinfunction "IO_L12N_T1U_N11_GC_66_J24") (pintype "passive"))
    )
    (net (code "200") (name "unconnected-(U2F-IO_L12P_T1U_N10_GC_66-PadJ23)") (class "Default")
      (node (ref "U2") (pin "J23") (pinfunction "IO_L12P_T1U_N10_GC_66_J23") (pintype "passive"))
    )
    (net (code "201") (name "unconnected-(U2F-IO_L14N_T2L_N3_GC_66-PadH24)") (class "Default")
      (node (ref "U2") (pin "H24") (pinfunction "IO_L14N_T2L_N3_GC_66_H24") (pintype "passive"))
    )
    (net (code "202") (name "unconnected-(U2F-IO_L14P_T2L_N2_GC_66-PadH23)") (class "Default")
      (node (ref "U2") (pin "H23") (pinfunction "IO_L14P_T2L_N2_GC_66_H23") (pintype "passive"))
    )
    (net (code "203") (name "unconnected-(U2F-IO_L16N_T2U_N7_QBC_AD3N_66-PadF25)") (class "Default")
      (node (ref "U2") (pin "F25") (pinfunction "IO_L16N_T2U_N7_QBC_AD3N_66_F25") (pintype "passive"))
    )
    (net (code "204") (name "unconnected-(U2F-IO_L16P_T2U_N6_QBC_AD3P_66-PadF24)") (class "Default")
      (node (ref "U2") (pin "F24") (pinfunction "IO_L16P_T2U_N6_QBC_AD3P_66_F24") (pintype "passive"))
    )
    (net (code "205") (name "unconnected-(U2F-IO_L19N_T3L_N1_DBC_AD9N_66-PadE26)") (class "Default")
      (node (ref "U2") (pin "E26") (pinfunction "IO_L19N_T3L_N1_DBC_AD9N_66_E26") (pintype "passive"))
    )
    (net (code "206") (name "unconnected-(U2G-IO_L8N_T1L_N3_AD5N_67-PadF19)") (class "Default")
      (node (ref "U2") (pin "F19") (pinfunction "IO_L8N_T1L_N3_AD5N_67_F19") (pintype "passive"))
    )
    (net (code "207") (name "unconnected-(U2G-IO_L8P_T1L_N2_AD5P_67-PadF18)") (class "Default")
      (node (ref "U2") (pin "F18") (pinfunction "IO_L8P_T1L_N2_AD5P_67_F18") (pintype "passive"))
    )
    (net (code "208") (name "unconnected-(U2G-IO_L11N_T1U_N9_GC_67-PadD18)") (class "Default")
      (node (ref "U2") (pin "D18") (pinfunction "IO_L11N_T1U_N9_GC_67_D18") (pintype "passive"))
    )
    (net (code "209") (name "unconnected-(U2G-IO_L21N_T3L_N5_AD8N_67-PadB24)") (class "Default")
      (node (ref "U2") (pin "B24") (pinfunction "IO_L21N_T3L_N5_AD8N_67_B24") (pintype "passive"))
    )
    (net (code "210") (name "unconnected-(U2G-IO_L21P_T3L_N4_AD8P_67-PadC23)") (class "Default")
      (node (ref "U2") (pin "C23") (pinfunction "IO_L21P_T3L_N4_AD8P_67_C23") (pintype "passive"))
    )
    (net (code "211") (name "unconnected-(U2G-IO_T1U_N12_67-PadG19)") (class "Default")
      (node (ref "U2") (pin "G19") (pinfunction "IO_T1U_N12_67_G19") (pintype "passive"))
    )
    (net (code "212") (name "unconnected-(U2G-IO_T2U_N12_67-PadB16)") (class "Default")
      (node (ref "U2") (pin "B16") (pinfunction "IO_T2U_N12_67_B16") (pintype "passive"))
    )
    (net (code "213") (name "unconnected-(U2G-IO_T3U_N12_67-PadE22)") (class "Default")
      (node (ref "U2") (pin "E22") (pinfunction "IO_T3U_N12_67_E22") (pintype "passive"))
    )
  )
)
